# ProProject_commutation_hand.net
KiCad netlist of a schematic drawn in EasyEDA Pro
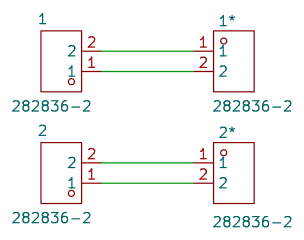
[diagram p0: schematic sheet]

(export (version "E")
  (design (tool "Eeschema 10.0.6"))
  (components
    (comp (ref "1")
      (value "282836-2")
      (footprint "easyedapro:CONN-TH_2P-P5.00_282836-2")
      (fields (field (name "Manufacturer") "TE Connectivity(泰科电子)"))
      (libsource (lib "easyedapro") (part "282836-2"))
    )
    (comp (ref "1*")
      (value "282836-2")
      (footprint "easyedapro:CONN-TH_2P-P5.00_282836-2")
      (fields (field (name "Manufacturer") "TE Connectivity(泰科电子)"))
      (libsource (lib "easyedapro") (part "282836-2"))
    )
    (comp (ref "2")
      (value "282836-2")
      (footprint "easyedapro:CONN-TH_2P-P5.00_282836-2")
      (fields (field (name "Manufacturer") "TE Connectivity(泰科电子)"))
      (libsource (lib "easyedapro") (part "282836-2"))
    )
    (comp (ref "2*")
      (value "282836-2")
      (footprint "easyedapro:CONN-TH_2P-P5.00_282836-2")
      (fields (field (name "Manufacturer") "TE Connectivity(泰科电子)"))
      (libsource (lib "easyedapro") (part "282836-2"))
    )
  )
  (nets
    (net (code "1") (name "Net-(1*-Pad1)") (class "Default")
      (node (ref "1") (pin "2") (pinfunction "2_2") (pintype "unspecified"))
      (node (ref "1*") (pin "1") (pinfunction "1_1") (pintype "unspecified"))
    )
    (net (code "2") (name "Net-(1*-Pad2)") (class "Default")
      (node (ref "1") (pin "1") (pinfunction "1_1") (pintype "unspecified"))
      (node (ref "1*") (pin "2") (pinfunction "2_2") (pintype "unspecified"))
    )
    (net (code "3") (name "Net-(2*-Pad1)") (class "Default")
      (node (ref "2") (pin "2") (pinfunction "2_2") (pintype "unspecified"))
      (node (ref "2*") (pin "1") (pinfunction "1_1") (pintype "unspecified"))
    )
    (net (code "4") (name "Net-(2*-Pad2)") (class "Default")
      (node (ref "2") (pin "1") (pinfunction "1_1") (pintype "unspecified"))
      (node (ref "2*") (pin "2") (pinfunction "2_2") (pintype "unspecified"))
    )
  )
)
